# BME280-Breakout_v11.net
KiCad netlist of a schematic drawn in EAGLE
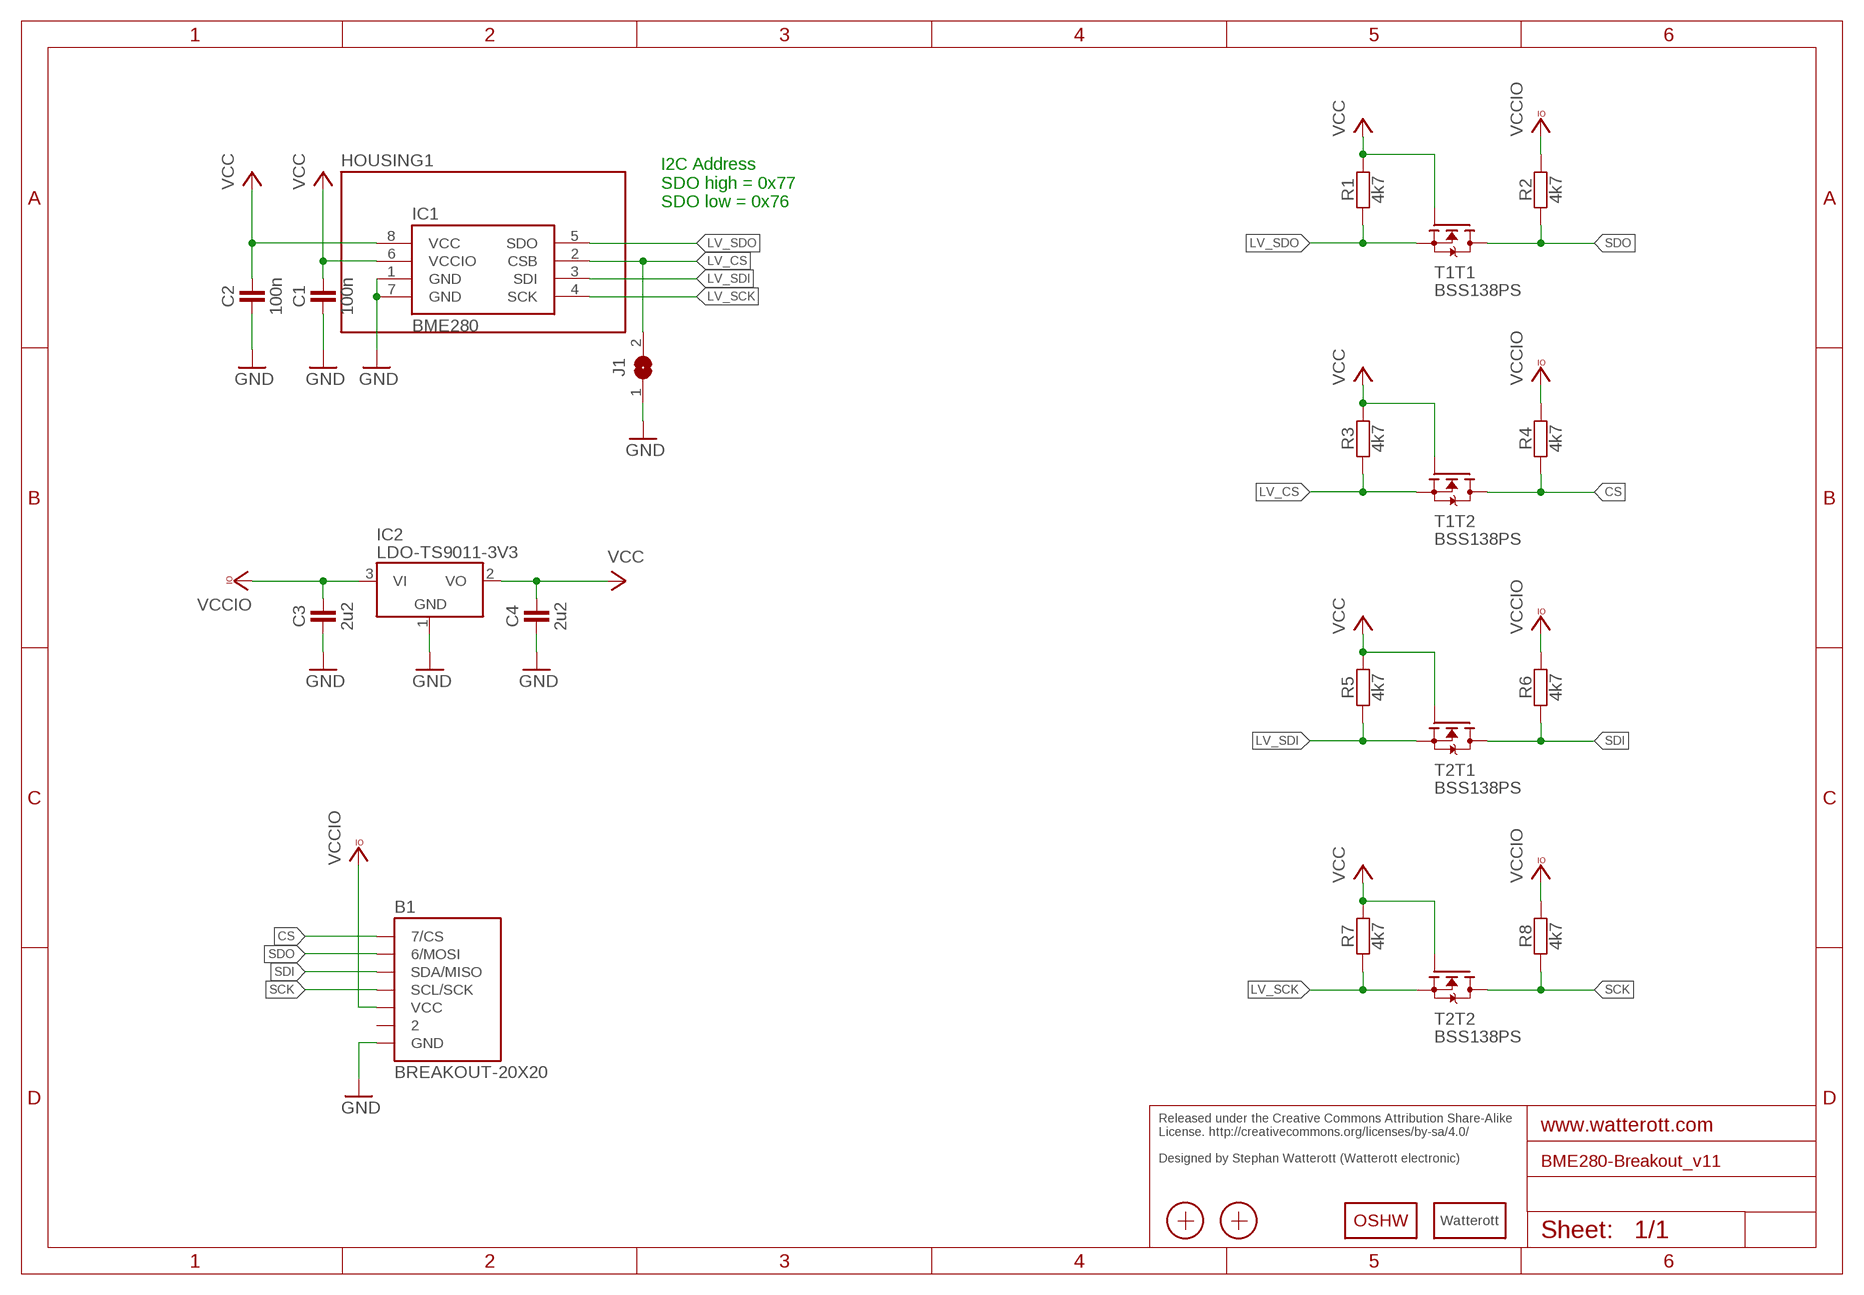
[diagram p0: schematic, sheet 1]

(export (version "E")
  (design (tool "Eeschema 10.0.6"))
  (components
    (comp (ref "B1")
      (value "BREAKOUT-20X20")
      (footprint "eagle-import:BREAKOUT-20X20")
      (libsource (lib "eagle-import") (part "BREAKOUT-20X20"))
    )
    (comp (ref "C1")
      (value "100n")
      (footprint "eagle-import:C0402")
      (libsource (lib "eagle-import") (part "CAPACITOR-0402"))
    )
    (comp (ref "C2")
      (value "100n")
      (footprint "eagle-import:C0402")
      (libsource (lib "eagle-import") (part "CAPACITOR-0402"))
    )
    (comp (ref "C3")
      (value "2u2")
      (footprint "eagle-import:C0402")
      (libsource (lib "eagle-import") (part "CAPACITOR-0402"))
    )
    (comp (ref "C4")
      (value "2u2")
      (footprint "eagle-import:C0402")
      (libsource (lib "eagle-import") (part "CAPACITOR-0402"))
    )
    (comp (ref "HOUSING1")
      (value "SF2")
      (footprint "eagle-import:SF2")
      (libsource (lib "eagle-import") (part "SF2"))
    )
    (comp (ref "IC1")
      (value "BME280")
      (footprint "eagle-import:CAVITY_MEMS")
      (libsource (lib "eagle-import") (part "BME280"))
    )
    (comp (ref "IC2")
      (value "LDO-TS9011-3V3")
      (footprint "eagle-import:SOT23")
      (libsource (lib "eagle-import") (part "LDO-TS9011-3V3"))
    )
    (comp (ref "J1")
      (value "JUMPER2-0603")
      (footprint "eagle-import:JUMPER2-0603")
      (libsource (lib "eagle-import") (part "JUMPER2-0603"))
    )
    (comp (ref "LOGO2")
      (value "OSHW_LOGOX0070")
      (footprint "eagle-import:OSHW_6X70")
      (libsource (lib "eagle-import") (part "OSHW_LOGOX0070"))
    )
    (comp (ref "LOGO3")
      (value "LOGO_SPARK-2")
      (footprint "eagle-import:SPARK_2MM")
      (libsource (lib "eagle-import") (part "LOGO_SPARK-2"))
    )
    (comp (ref "R1")
      (value "4k7")
      (footprint "eagle-import:C0402")
      (libsource (lib "eagle-import") (part "RESISTOR-0402"))
    )
    (comp (ref "R2")
      (value "4k7")
      (footprint "eagle-import:C0402")
      (libsource (lib "eagle-import") (part "RESISTOR-0402"))
    )
    (comp (ref "R3")
      (value "4k7")
      (footprint "eagle-import:C0402")
      (libsource (lib "eagle-import") (part "RESISTOR-0402"))
    )
    (comp (ref "R4")
      (value "4k7")
      (footprint "eagle-import:C0402")
      (libsource (lib "eagle-import") (part "RESISTOR-0402"))
    )
    (comp (ref "R5")
      (value "4k7")
      (footprint "eagle-import:C0402")
      (libsource (lib "eagle-import") (part "RESISTOR-0402"))
    )
    (comp (ref "R6")
      (value "4k7")
      (footprint "eagle-import:C0402")
      (libsource (lib "eagle-import") (part "RESISTOR-0402"))
    )
    (comp (ref "R7")
      (value "4k7")
      (footprint "eagle-import:C0402")
      (libsource (lib "eagle-import") (part "RESISTOR-0402"))
    )
    (comp (ref "R8")
      (value "4k7")
      (footprint "eagle-import:C0402")
      (libsource (lib "eagle-import") (part "RESISTOR-0402"))
    )
    (comp (ref "T1")
      (value "BSS138PS")
      (footprint "eagle-import:SOT363")
      (libsource (lib "eagle-import") (part "BSS138PS"))
    )
    (comp (ref "T2")
      (value "BSS138PS")
      (footprint "eagle-import:SOT363")
      (libsource (lib "eagle-import") (part "BSS138PS"))
    )
    (comp (ref "X1")
      (value "PASSER-07")
      (footprint "eagle-import:PASSER_07MM")
      (libsource (lib "eagle-import") (part "PASSER-07"))
    )
    (comp (ref "X2")
      (value "PASSER-07")
      (footprint "eagle-import:PASSER_07MM")
      (libsource (lib "eagle-import") (part "PASSER-07"))
    )
  )
  (nets
    (net (code "1") (name "CS") (class "Default")
      (node (ref "B1") (pin "CS") (pinfunction "7/CS_CS") (pintype "bidirectional"))
      (node (ref "R4") (pin "1") (pinfunction "1_1") (pintype "passive"))
      (node (ref "T1") (pin "3") (pinfunction "D_3") (pintype "passive"))
    )
    (net (code "2") (name "GND") (class "Default")
      (node (ref "B1") (pin "GND") (pinfunction "GND_GND") (pintype "power_in"))
      (node (ref "C1") (pin "1") (pinfunction "1_1") (pintype "passive"))
      (node (ref "C2") (pin "1") (pinfunction "1_1") (pintype "passive"))
      (node (ref "C3") (pin "1") (pinfunction "1_1") (pintype "passive"))
      (node (ref "C4") (pin "1") (pinfunction "1_1") (pintype "passive"))
      (node (ref "IC1") (pin "1") (pinfunction "GND_1") (pintype "power_in"))
      (node (ref "IC1") (pin "7") (pinfunction "GND_7") (pintype "power_in"))
      (node (ref "IC2") (pin "1") (pinfunction "GND_1") (pintype "passive"))
      (node (ref "J1") (pin "1") (pinfunction "1_1") (pintype "passive"))
    )
    (net (code "3") (name "LV_CS") (class "Default")
      (node (ref "IC1") (pin "2") (pinfunction "CSB_2") (pintype "input"))
      (node (ref "J1") (pin "2") (pinfunction "2_2") (pintype "passive"))
      (node (ref "R3") (pin "1") (pinfunction "1_1") (pintype "passive"))
      (node (ref "T1") (pin "4") (pinfunction "S_4") (pintype "passive"))
    )
    (net (code "4") (name "LV_SCK") (class "Default")
      (node (ref "IC1") (pin "4") (pinfunction "SCK_4") (pintype "bidirectional"))
      (node (ref "R7") (pin "1") (pinfunction "1_1") (pintype "passive"))
      (node (ref "T2") (pin "4") (pinfunction "S_4") (pintype "passive"))
    )
    (net (code "5") (name "LV_SDI") (class "Default")
      (node (ref "IC1") (pin "3") (pinfunction "SDI_3") (pintype "bidirectional"))
      (node (ref "R5") (pin "1") (pinfunction "1_1") (pintype "passive"))
      (node (ref "T2") (pin "1") (pinfunction "S_1") (pintype "passive"))
    )
    (net (code "6") (name "LV_SDO") (class "Default")
      (node (ref "IC1") (pin "5") (pinfunction "SDO_5") (pintype "bidirectional"))
      (node (ref "R1") (pin "1") (pinfunction "1_1") (pintype "passive"))
      (node (ref "T1") (pin "1") (pinfunction "S_1") (pintype "passive"))
    )
    (net (code "7") (name "SCK") (class "Default")
      (node (ref "B1") (pin "SCL/SCK") (pinfunction "SCL/SCK_SCL/SCK") (pintype "bidirectional"))
      (node (ref "R8") (pin "1") (pinfunction "1_1") (pintype "passive"))
      (node (ref "T2") (pin "3") (pinfunction "D_3") (pintype "passive"))
    )
    (net (code "8") (name "SDI") (class "Default")
      (node (ref "B1") (pin "SDA/MISO") (pinfunction "SDA/MISO_SDA/MISO") (pintype "bidirectional"))
      (node (ref "R6") (pin "1") (pinfunction "1_1") (pintype "passive"))
      (node (ref "T2") (pin "6") (pinfunction "D_6") (pintype "passive"))
    )
    (net (code "9") (name "SDO") (class "Default")
      (node (ref "B1") (pin "MOSI") (pinfunction "6/MOSI_MOSI") (pintype "bidirectional"))
      (node (ref "R2") (pin "1") (pinfunction "1_1") (pintype "passive"))
      (node (ref "T1") (pin "6") (pinfunction "D_6") (pintype "passive"))
    )
    (net (code "10") (name "VCC") (class "Default")
      (node (ref "C1") (pin "2") (pinfunction "2_2") (pintype "passive"))
      (node (ref "C2") (pin "2") (pinfunction "2_2") (pintype "passive"))
      (node (ref "C4") (pin "2") (pinfunction "2_2") (pintype "passive"))
      (node (ref "IC1") (pin "6") (pinfunction "VCCIO_6") (pintype "power_in"))
      (node (ref "IC1") (pin "8") (pinfunction "VCC_8") (pintype "power_in"))
      (node (ref "IC2") (pin "2") (pinfunction "VO_2") (pintype "passive"))
      (node (ref "R1") (pin "2") (pinfunction "2_2") (pintype "passive"))
      (node (ref "R3") (pin "2") (pinfunction "2_2") (pintype "passive"))
      (node (ref "R5") (pin "2") (pinfunction "2_2") (pintype "passive"))
      (node (ref "R7") (pin "2") (pinfunction "2_2") (pintype "passive"))
      (node (ref "T1") (pin "2") (pinfunction "G_2") (pintype "passive"))
      (node (ref "T1") (pin "5") (pinfunction "G_5") (pintype "passive"))
      (node (ref "T2") (pin "2") (pinfunction "G_2") (pintype "passive"))
      (node (ref "T2") (pin "5") (pinfunction "G_5") (pintype "passive"))
    )
    (net (code "11") (name "VCCIO") (class "Default")
      (node (ref "B1") (pin "VCC") (pinfunction "VCC_VCC") (pintype "power_in"))
      (node (ref "C3") (pin "2") (pinfunction "2_2") (pintype "passive"))
      (node (ref "IC2") (pin "3") (pinfunction "VI_3") (pintype "input"))
      (node (ref "R2") (pin "2") (pinfunction "2_2") (pintype "passive"))
      (node (ref "R4") (pin "2") (pinfunction "2_2") (pintype "passive"))
      (node (ref "R6") (pin "2") (pinfunction "2_2") (pintype "passive"))
      (node (ref "R8") (pin "2") (pinfunction "2_2") (pintype "passive"))
    )
    (net (code "12") (name "unconnected-(B1-Pad2)") (class "Default")
      (node (ref "B1") (pin "2") (pinfunction "2_2") (pintype "bidirectional"))
    )
  )
)
